# Top.net
KiCad netlist of a schematic drawn in EAGLE
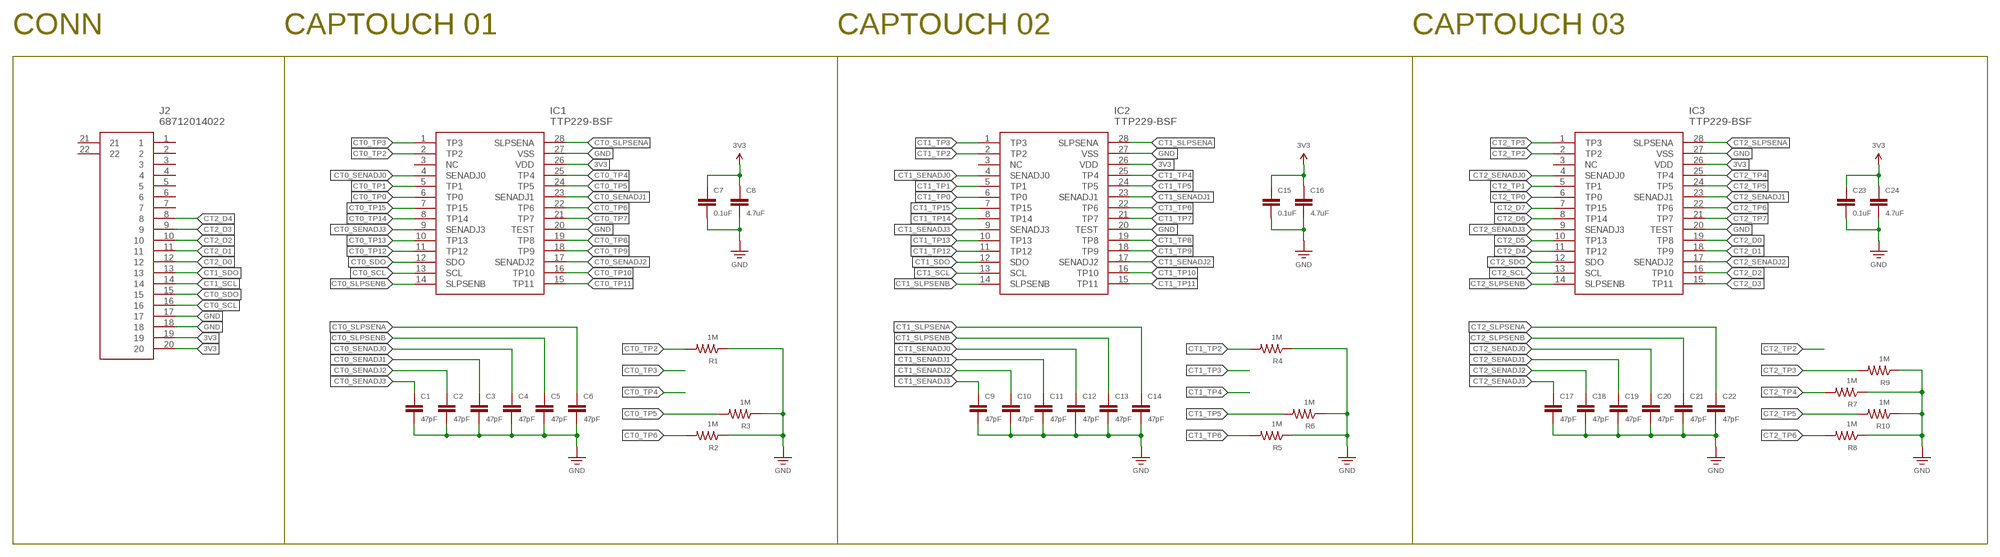
[diagram p0: schematic, sheet 1]

(export (version "E")
  (design (tool "Eeschema 10.0.6"))
  (components
    (comp (ref "C1")
      (value "47pF")
      (footprint "eagle-import:CAP-0603")
      (libsource (lib "eagle-import") (part "CAP-0603"))
    )
    (comp (ref "C2")
      (value "47pF")
      (footprint "eagle-import:CAP-0603")
      (libsource (lib "eagle-import") (part "CAP-0603"))
    )
    (comp (ref "C3")
      (value "47pF")
      (footprint "eagle-import:CAP-0603")
      (libsource (lib "eagle-import") (part "CAP-0603"))
    )
    (comp (ref "C4")
      (value "47pF")
      (footprint "eagle-import:CAP-0603")
      (libsource (lib "eagle-import") (part "CAP-0603"))
    )
    (comp (ref "C5")
      (value "47pF")
      (footprint "eagle-import:CAP-0603")
      (libsource (lib "eagle-import") (part "CAP-0603"))
    )
    (comp (ref "C6")
      (value "47pF")
      (footprint "eagle-import:CAP-0603")
      (libsource (lib "eagle-import") (part "CAP-0603"))
    )
    (comp (ref "C7")
      (value "0.1uF")
      (footprint "eagle-import:CAP-0603")
      (libsource (lib "eagle-import") (part "CAP-0603"))
    )
    (comp (ref "C8")
      (value "4.7uF")
      (footprint "eagle-import:CAP-0603")
      (libsource (lib "eagle-import") (part "CAP-0603"))
    )
    (comp (ref "C9")
      (value "47pF")
      (footprint "eagle-import:CAP-0603")
      (libsource (lib "eagle-import") (part "CAP-0603"))
    )
    (comp (ref "C10")
      (value "47pF")
      (footprint "eagle-import:CAP-0603")
      (libsource (lib "eagle-import") (part "CAP-0603"))
    )
    (comp (ref "C11")
      (value "47pF")
      (footprint "eagle-import:CAP-0603")
      (libsource (lib "eagle-import") (part "CAP-0603"))
    )
    (comp (ref "C12")
      (value "47pF")
      (footprint "eagle-import:CAP-0603")
      (libsource (lib "eagle-import") (part "CAP-0603"))
    )
    (comp (ref "C13")
      (value "47pF")
      (footprint "eagle-import:CAP-0603")
      (libsource (lib "eagle-import") (part "CAP-0603"))
    )
    (comp (ref "C14")
      (value "47pF")
      (footprint "eagle-import:CAP-0603")
      (libsource (lib "eagle-import") (part "CAP-0603"))
    )
    (comp (ref "C15")
      (value "0.1uF")
      (footprint "eagle-import:CAP-0603")
      (libsource (lib "eagle-import") (part "CAP-0603"))
    )
    (comp (ref "C16")
      (value "4.7uF")
      (footprint "eagle-import:CAP-0603")
      (libsource (lib "eagle-import") (part "CAP-0603"))
    )
    (comp (ref "C17")
      (value "47pF")
      (footprint "eagle-import:CAP-0603")
      (libsource (lib "eagle-import") (part "CAP-0603"))
    )
    (comp (ref "C18")
      (value "47pF")
      (footprint "eagle-import:CAP-0603")
      (libsource (lib "eagle-import") (part "CAP-0603"))
    )
    (comp (ref "C19")
      (value "47pF")
      (footprint "eagle-import:CAP-0603")
      (libsource (lib "eagle-import") (part "CAP-0603"))
    )
    (comp (ref "C20")
      (value "47pF")
      (footprint "eagle-import:CAP-0603")
      (libsource (lib "eagle-import") (part "CAP-0603"))
    )
    (comp (ref "C21")
      (value "47pF")
      (footprint "eagle-import:CAP-0603")
      (libsource (lib "eagle-import") (part "CAP-0603"))
    )
    (comp (ref "C22")
      (value "47pF")
      (footprint "eagle-import:CAP-0603")
      (libsource (lib "eagle-import") (part "CAP-0603"))
    )
    (comp (ref "C23")
      (value "0.1uF")
      (footprint "eagle-import:CAP-0603")
      (libsource (lib "eagle-import") (part "CAP-0603"))
    )
    (comp (ref "C24")
      (value "4.7uF")
      (footprint "eagle-import:CAP-0603")
      (libsource (lib "eagle-import") (part "CAP-0603"))
    )
    (comp (ref "IC1")
      (value "TTP229-BSF")
      (footprint "eagle-import:SOP64P600X175-28N")
      (libsource (lib "eagle-import") (part "TTP229-BSF"))
    )
    (comp (ref "IC2")
      (value "TTP229-BSF")
      (footprint "eagle-import:SOP64P600X175-28N")
      (libsource (lib "eagle-import") (part "TTP229-BSF"))
    )
    (comp (ref "IC3")
      (value "TTP229-BSF")
      (footprint "eagle-import:SOP64P600X175-28N")
      (libsource (lib "eagle-import") (part "TTP229-BSF"))
    )
    (comp (ref "J2")
      (value "68712014022")
      (footprint "eagle-import:68712014022")
      (fields (field (name "MOUSER_PART_NUMBER") "710-68712014022"))
      (libsource (lib "eagle-import") (part "68712014022"))
    )
    (comp (ref "R1")
      (value "1M")
      (footprint "eagle-import:RES-0603")
      (libsource (lib "eagle-import") (part "RES-0603"))
    )
    (comp (ref "R2")
      (value "1M")
      (footprint "eagle-import:RES-0603")
      (libsource (lib "eagle-import") (part "RES-0603"))
    )
    (comp (ref "R3")
      (value "1M")
      (footprint "eagle-import:RES-0603")
      (libsource (lib "eagle-import") (part "RES-0603"))
    )
    (comp (ref "R4")
      (value "1M")
      (footprint "eagle-import:RES-0603")
      (libsource (lib "eagle-import") (part "RES-0603"))
    )
    (comp (ref "R5")
      (value "1M")
      (footprint "eagle-import:RES-0603")
      (libsource (lib "eagle-import") (part "RES-0603"))
    )
    (comp (ref "R6")
      (value "1M")
      (footprint "eagle-import:RES-0603")
      (libsource (lib "eagle-import") (part "RES-0603"))
    )
    (comp (ref "R7")
      (value "1M")
      (footprint "eagle-import:RES-0603")
      (libsource (lib "eagle-import") (part "RES-0603"))
    )
    (comp (ref "R8")
      (value "1M")
      (footprint "eagle-import:RES-0603")
      (libsource (lib "eagle-import") (part "RES-0603"))
    )
    (comp (ref "R9")
      (value "1M")
      (footprint "eagle-import:RES-0603")
      (libsource (lib "eagle-import") (part "RES-0603"))
    )
    (comp (ref "R10")
      (value "1M")
      (footprint "eagle-import:RES-0603")
      (libsource (lib "eagle-import") (part "RES-0603"))
    )
  )
  (nets
    (net (code "1") (name "3V3") (class "Default")
      (node (ref "C15") (pin "P$1") (pinfunction "1_P$1") (pintype "passive"))
      (node (ref "C16") (pin "P$1") (pinfunction "1_P$1") (pintype "passive"))
      (node (ref "C23") (pin "P$1") (pinfunction "1_P$1") (pintype "passive"))
      (node (ref "C24") (pin "P$1") (pinfunction "1_P$1") (pintype "passive"))
      (node (ref "C7") (pin "P$1") (pinfunction "1_P$1") (pintype "passive"))
      (node (ref "C8") (pin "P$1") (pinfunction "1_P$1") (pintype "passive"))
      (node (ref "IC1") (pin "26") (pinfunction "VDD_26") (pintype "bidirectional"))
      (node (ref "IC2") (pin "26") (pinfunction "VDD_26") (pintype "bidirectional"))
      (node (ref "IC3") (pin "26") (pinfunction "VDD_26") (pintype "bidirectional"))
      (node (ref "J2") (pin "19") (pinfunction "19_19") (pintype "bidirectional"))
      (node (ref "J2") (pin "20") (pinfunction "20_20") (pintype "bidirectional"))
    )
    (net (code "2") (name "CT0_SCL") (class "Default")
      (node (ref "IC1") (pin "13") (pinfunction "SCL_13") (pintype "bidirectional"))
      (node (ref "J2") (pin "16") (pinfunction "16_16") (pintype "bidirectional"))
    )
    (net (code "3") (name "CT0_SDO") (class "Default")
      (node (ref "IC1") (pin "12") (pinfunction "SDO_12") (pintype "bidirectional"))
      (node (ref "J2") (pin "15") (pinfunction "15_15") (pintype "bidirectional"))
    )
    (net (code "4") (name "CT0_SENADJ0") (class "Default")
      (node (ref "C4") (pin "P$1") (pinfunction "1_P$1") (pintype "passive"))
      (node (ref "IC1") (pin "4") (pinfunction "SENADJ0_4") (pintype "bidirectional"))
    )
    (net (code "5") (name "CT0_SENADJ1") (class "Default")
      (node (ref "C3") (pin "P$1") (pinfunction "1_P$1") (pintype "passive"))
      (node (ref "IC1") (pin "23") (pinfunction "SENADJ1_23") (pintype "bidirectional"))
    )
    (net (code "6") (name "CT0_SENADJ2") (class "Default")
      (node (ref "C2") (pin "P$1") (pinfunction "1_P$1") (pintype "passive"))
      (node (ref "IC1") (pin "17") (pinfunction "SENADJ2_17") (pintype "bidirectional"))
    )
    (net (code "7") (name "CT0_SENADJ3") (class "Default")
      (node (ref "C1") (pin "P$1") (pinfunction "1_P$1") (pintype "passive"))
      (node (ref "IC1") (pin "9") (pinfunction "SENADJ3_9") (pintype "bidirectional"))
    )
    (net (code "8") (name "CT0_SLPSENA") (class "Default")
      (node (ref "C6") (pin "P$1") (pinfunction "1_P$1") (pintype "passive"))
      (node (ref "IC1") (pin "28") (pinfunction "SLPSENA_28") (pintype "bidirectional"))
    )
    (net (code "9") (name "CT0_SLPSENB") (class "Default")
      (node (ref "C5") (pin "P$1") (pinfunction "1_P$1") (pintype "passive"))
      (node (ref "IC1") (pin "14") (pinfunction "SLPSENB_14") (pintype "bidirectional"))
    )
    (net (code "10") (name "CT0_TP0") (class "Default")
      (node (ref "IC1") (pin "6") (pinfunction "TP0_6") (pintype "bidirectional"))
    )
    (net (code "11") (name "CT0_TP1") (class "Default")
      (node (ref "IC1") (pin "5") (pinfunction "TP1_5") (pintype "bidirectional"))
    )
    (net (code "12") (name "CT0_TP2") (class "Default")
      (node (ref "IC1") (pin "2") (pinfunction "TP2_2") (pintype "bidirectional"))
      (node (ref "R1") (pin "P$2") (pinfunction "2_P$2") (pintype "passive"))
    )
    (net (code "13") (name "CT0_TP3") (class "Default")
      (node (ref "IC1") (pin "1") (pinfunction "TP3_1") (pintype "bidirectional"))
    )
    (net (code "14") (name "CT0_TP4") (class "Default")
      (node (ref "IC1") (pin "25") (pinfunction "TP4_25") (pintype "bidirectional"))
    )
    (net (code "15") (name "CT0_TP5") (class "Default")
      (node (ref "IC1") (pin "24") (pinfunction "TP5_24") (pintype "bidirectional"))
      (node (ref "R3") (pin "P$2") (pinfunction "2_P$2") (pintype "passive"))
    )
    (net (code "16") (name "CT0_TP6") (class "Default")
      (node (ref "IC1") (pin "22") (pinfunction "TP6_22") (pintype "bidirectional"))
      (node (ref "R2") (pin "P$2") (pinfunction "2_P$2") (pintype "passive"))
    )
    (net (code "17") (name "CT0_TP7") (class "Default")
      (node (ref "IC1") (pin "21") (pinfunction "TP7_21") (pintype "bidirectional"))
    )
    (net (code "18") (name "CT0_TP8") (class "Default")
      (node (ref "IC1") (pin "19") (pinfunction "TP8_19") (pintype "bidirectional"))
    )
    (net (code "19") (name "CT0_TP9") (class "Default")
      (node (ref "IC1") (pin "18") (pinfunction "TP9_18") (pintype "bidirectional"))
    )
    (net (code "20") (name "CT0_TP10") (class "Default")
      (node (ref "IC1") (pin "16") (pinfunction "TP10_16") (pintype "bidirectional"))
    )
    (net (code "21") (name "CT0_TP11") (class "Default")
      (node (ref "IC1") (pin "15") (pinfunction "TP11_15") (pintype "bidirectional"))
    )
    (net (code "22") (name "CT0_TP12") (class "Default")
      (node (ref "IC1") (pin "11") (pinfunction "TP12_11") (pintype "bidirectional"))
    )
    (net (code "23") (name "CT0_TP13") (class "Default")
      (node (ref "IC1") (pin "10") (pinfunction "TP13_10") (pintype "bidirectional"))
    )
    (net (code "24") (name "CT0_TP14") (class "Default")
      (node (ref "IC1") (pin "8") (pinfunction "TP14_8") (pintype "bidirectional"))
    )
    (net (code "25") (name "CT0_TP15") (class "Default")
      (node (ref "IC1") (pin "7") (pinfunction "TP15_7") (pintype "bidirectional"))
    )
    (net (code "26") (name "CT1_SCL") (class "Default")
      (node (ref "IC2") (pin "13") (pinfunction "SCL_13") (pintype "bidirectional"))
      (node (ref "J2") (pin "14") (pinfunction "14_14") (pintype "bidirectional"))
    )
    (net (code "27") (name "CT1_SDO") (class "Default")
      (node (ref "IC2") (pin "12") (pinfunction "SDO_12") (pintype "bidirectional"))
      (node (ref "J2") (pin "13") (pinfunction "13_13") (pintype "bidirectional"))
    )
    (net (code "28") (name "CT1_SENADJ0") (class "Default")
      (node (ref "C12") (pin "P$1") (pinfunction "1_P$1") (pintype "passive"))
      (node (ref "IC2") (pin "4") (pinfunction "SENADJ0_4") (pintype "bidirectional"))
    )
    (net (code "29") (name "CT1_SENADJ1") (class "Default")
      (node (ref "C11") (pin "P$1") (pinfunction "1_P$1") (pintype "passive"))
      (node (ref "IC2") (pin "23") (pinfunction "SENADJ1_23") (pintype "bidirectional"))
    )
    (net (code "30") (name "CT1_SENADJ2") (class "Default")
      (node (ref "C10") (pin "P$1") (pinfunction "1_P$1") (pintype "passive"))
      (node (ref "IC2") (pin "17") (pinfunction "SENADJ2_17") (pintype "bidirectional"))
    )
    (net (code "31") (name "CT1_SENADJ3") (class "Default")
      (node (ref "C9") (pin "P$1") (pinfunction "1_P$1") (pintype "passive"))
      (node (ref "IC2") (pin "9") (pinfunction "SENADJ3_9") (pintype "bidirectional"))
    )
    (net (code "32") (name "CT1_SLPSENA") (class "Default")
      (node (ref "C14") (pin "P$1") (pinfunction "1_P$1") (pintype "passive"))
      (node (ref "IC2") (pin "28") (pinfunction "SLPSENA_28") (pintype "bidirectional"))
    )
    (net (code "33") (name "CT1_SLPSENB") (class "Default")
      (node (ref "C13") (pin "P$1") (pinfunction "1_P$1") (pintype "passive"))
      (node (ref "IC2") (pin "14") (pinfunction "SLPSENB_14") (pintype "bidirectional"))
    )
    (net (code "34") (name "CT1_TP0") (class "Default")
      (node (ref "IC2") (pin "6") (pinfunction "TP0_6") (pintype "bidirectional"))
    )
    (net (code "35") (name "CT1_TP1") (class "Default")
      (node (ref "IC2") (pin "5") (pinfunction "TP1_5") (pintype "bidirectional"))
    )
    (net (code "36") (name "CT1_TP2") (class "Default")
      (node (ref "IC2") (pin "2") (pinfunction "TP2_2") (pintype "bidirectional"))
      (node (ref "R4") (pin "P$2") (pinfunction "2_P$2") (pintype "passive"))
    )
    (net (code "37") (name "CT1_TP3") (class "Default")
      (node (ref "IC2") (pin "1") (pinfunction "TP3_1") (pintype "bidirectional"))
    )
    (net (code "38") (name "CT1_TP4") (class "Default")
      (node (ref "IC2") (pin "25") (pinfunction "TP4_25") (pintype "bidirectional"))
    )
    (net (code "39") (name "CT1_TP5") (class "Default")
      (node (ref "IC2") (pin "24") (pinfunction "TP5_24") (pintype "bidirectional"))
      (node (ref "R6") (pin "P$2") (pinfunction "2_P$2") (pintype "passive"))
    )
    (net (code "40") (name "CT1_TP6") (class "Default")
      (node (ref "IC2") (pin "22") (pinfunction "TP6_22") (pintype "bidirectional"))
      (node (ref "R5") (pin "P$2") (pinfunction "2_P$2") (pintype "passive"))
    )
    (net (code "41") (name "CT1_TP7") (class "Default")
      (node (ref "IC2") (pin "21") (pinfunction "TP7_21") (pintype "bidirectional"))
    )
    (net (code "42") (name "CT1_TP8") (class "Default")
      (node (ref "IC2") (pin "19") (pinfunction "TP8_19") (pintype "bidirectional"))
    )
    (net (code "43") (name "CT1_TP9") (class "Default")
      (node (ref "IC2") (pin "18") (pinfunction "TP9_18") (pintype "bidirectional"))
    )
    (net (code "44") (name "CT1_TP10") (class "Default")
      (node (ref "IC2") (pin "16") (pinfunction "TP10_16") (pintype "bidirectional"))
    )
    (net (code "45") (name "CT1_TP11") (class "Default")
      (node (ref "IC2") (pin "15") (pinfunction "TP11_15") (pintype "bidirectional"))
    )
    (net (code "46") (name "CT1_TP12") (class "Default")
      (node (ref "IC2") (pin "11") (pinfunction "TP12_11") (pintype "bidirectional"))
    )
    (net (code "47") (name "CT1_TP13") (class "Default")
      (node (ref "IC2") (pin "10") (pinfunction "TP13_10") (pintype "bidirectional"))
    )
    (net (code "48") (name "CT1_TP14") (class "Default")
      (node (ref "IC2") (pin "8") (pinfunction "TP14_8") (pintype "bidirectional"))
    )
    (net (code "49") (name "CT1_TP15") (class "Default")
      (node (ref "IC2") (pin "7") (pinfunction "TP15_7") (pintype "bidirectional"))
    )
    (net (code "50") (name "CT2_D0") (class "Default")
      (node (ref "IC3") (pin "19") (pinfunction "TP8_19") (pintype "bidirectional"))
      (node (ref "J2") (pin "12") (pinfunction "12_12") (pintype "bidirectional"))
    )
    (net (code "51") (name "CT2_D1") (class "Default")
      (node (ref "IC3") (pin "18") (pinfunction "TP9_18") (pintype "bidirectional"))
      (node (ref "J2") (pin "11") (pinfunction "11_11") (pintype "bidirectional"))
    )
    (net (code "52") (name "CT2_D2") (class "Default")
      (node (ref "IC3") (pin "16") (pinfunction "TP10_16") (pintype "bidirectional"))
      (node (ref "J2") (pin "10") (pinfunction "10_10") (pintype "bidirectional"))
    )
    (net (code "53") (name "CT2_D3") (class "Default")
      (node (ref "IC3") (pin "15") (pinfunction "TP11_15") (pintype "bidirectional"))
      (node (ref "J2") (pin "9") (pinfunction "9_9") (pintype "bidirectional"))
    )
    (net (code "54") (name "CT2_D4") (class "Default")
      (node (ref "IC3") (pin "11") (pinfunction "TP12_11") (pintype "bidirectional"))
      (node (ref "J2") (pin "8") (pinfunction "8_8") (pintype "bidirectional"))
    )
    (net (code "55") (name "CT2_D5") (class "Default")
      (node (ref "IC3") (pin "10") (pinfunction "TP13_10") (pintype "bidirectional"))
    )
    (net (code "56") (name "CT2_D6") (class "Default")
      (node (ref "IC3") (pin "8") (pinfunction "TP14_8") (pintype "bidirectional"))
    )
    (net (code "57") (name "CT2_D7") (class "Default")
      (node (ref "IC3") (pin "7") (pinfunction "TP15_7") (pintype "bidirectional"))
    )
    (net (code "58") (name "CT2_SCL") (class "Default")
      (node (ref "IC3") (pin "13") (pinfunction "SCL_13") (pintype "bidirectional"))
    )
    (net (code "59") (name "CT2_SDO") (class "Default")
      (node (ref "IC3") (pin "12") (pinfunction "SDO_12") (pintype "bidirectional"))
    )
    (net (code "60") (name "CT2_SENADJ0") (class "Default")
      (node (ref "C20") (pin "P$1") (pinfunction "1_P$1") (pintype "passive"))
      (node (ref "IC3") (pin "4") (pinfunction "SENADJ0_4") (pintype "bidirectional"))
    )
    (net (code "61") (name "CT2_SENADJ1") (class "Default")
      (node (ref "C19") (pin "P$1") (pinfunction "1_P$1") (pintype "passive"))
      (node (ref "IC3") (pin "23") (pinfunction "SENADJ1_23") (pintype "bidirectional"))
    )
    (net (code "62") (name "CT2_SENADJ2") (class "Default")
      (node (ref "C18") (pin "P$1") (pinfunction "1_P$1") (pintype "passive"))
      (node (ref "IC3") (pin "17") (pinfunction "SENADJ2_17") (pintype "bidirectional"))
    )
    (net (code "63") (name "CT2_SENADJ3") (class "Default")
      (node (ref "C17") (pin "P$1") (pinfunction "1_P$1") (pintype "passive"))
      (node (ref "IC3") (pin "9") (pinfunction "SENADJ3_9") (pintype "bidirectional"))
    )
    (net (code "64") (name "CT2_SLPSENA") (class "Default")
      (node (ref "C22") (pin "P$1") (pinfunction "1_P$1") (pintype "passive"))
      (node (ref "IC3") (pin "28") (pinfunction "SLPSENA_28") (pintype "bidirectional"))
    )
    (net (code "65") (name "CT2_SLPSENB") (class "Default")
      (node (ref "C21") (pin "P$1") (pinfunction "1_P$1") (pintype "passive"))
      (node (ref "IC3") (pin "14") (pinfunction "SLPSENB_14") (pintype "bidirectional"))
    )
    (net (code "66") (name "CT2_TP0") (class "Default")
      (node (ref "IC3") (pin "6") (pinfunction "TP0_6") (pintype "bidirectional"))
    )
    (net (code "67") (name "CT2_TP1") (class "Default")
      (node (ref "IC3") (pin "5") (pinfunction "TP1_5") (pintype "bidirectional"))
    )
    (net (code "68") (name "CT2_TP2") (class "Default")
      (node (ref "IC3") (pin "2") (pinfunction "TP2_2") (pintype "bidirectional"))
    )
    (net (code "69") (name "CT2_TP3") (class "Default")
      (node (ref "IC3") (pin "1") (pinfunction "TP3_1") (pintype "bidirectional"))
      (node (ref "R9") (pin "P$2") (pinfunction "2_P$2") (pintype "passive"))
    )
    (net (code "70") (name "CT2_TP4") (class "Default")
      (node (ref "IC3") (pin "25") (pinfunction "TP4_25") (pintype "bidirectional"))
      (node (ref "R7") (pin "P$2") (pinfunction "2_P$2") (pintype "passive"))
    )
    (net (code "71") (name "CT2_TP5") (class "Default")
      (node (ref "IC3") (pin "24") (pinfunction "TP5_24") (pintype "bidirectional"))
      (node (ref "R10") (pin "P$2") (pinfunction "2_P$2") (pintype "passive"))
    )
    (net (code "72") (name "CT2_TP6") (class "Default")
      (node (ref "IC3") (pin "22") (pinfunction "TP6_22") (pintype "bidirectional"))
      (node (ref "R8") (pin "P$2") (pinfunction "2_P$2") (pintype "passive"))
    )
    (net (code "73") (name "CT2_TP7") (class "Default")
      (node (ref "IC3") (pin "21") (pinfunction "TP7_21") (pintype "bidirectional"))
    )
    (net (code "74") (name "GND") (class "Default")
      (node (ref "C1") (pin "P$2") (pinfunction "2_P$2") (pintype "passive"))
      (node (ref "C10") (pin "P$2") (pinfunction "2_P$2") (pintype "passive"))
      (node (ref "C11") (pin "P$2") (pinfunction "2_P$2") (pintype "passive"))
      (node (ref "C12") (pin "P$2") (pinfunction "2_P$2") (pintype "passive"))
      (node (ref "C13") (pin "P$2") (pinfunction "2_P$2") (pintype "passive"))
      (node (ref "C14") (pin "P$2") (pinfunction "2_P$2") (pintype "passive"))
      (node (ref "C15") (pin "P$2") (pinfunction "2_P$2") (pintype "passive"))
      (node (ref "C16") (pin "P$2") (pinfunction "2_P$2") (pintype "passive"))
      (node (ref "C17") (pin "P$2") (pinfunction "2_P$2") (pintype "passive"))
      (node (ref "C18") (pin "P$2") (pinfunction "2_P$2") (pintype "passive"))
      (node (ref "C19") (pin "P$2") (pinfunction "2_P$2") (pintype "passive"))
      (node (ref "C2") (pin "P$2") (pinfunction "2_P$2") (pintype "passive"))
      (node (ref "C20") (pin "P$2") (pinfunction "2_P$2") (pintype "passive"))
      (node (ref "C21") (pin "P$2") (pinfunction "2_P$2") (pintype "passive"))
      (node (ref "C22") (pin "P$2") (pinfunction "2_P$2") (pintype "passive"))
      (node (ref "C23") (pin "P$2") (pinfunction "2_P$2") (pintype "passive"))
      (node (ref "C24") (pin "P$2") (pinfunction "2_P$2") (pintype "passive"))
      (node (ref "C3") (pin "P$2") (pinfunction "2_P$2") (pintype "passive"))
      (node (ref "C4") (pin "P$2") (pinfunction "2_P$2") (pintype "passive"))
      (node (ref "C5") (pin "P$2") (pinfunction "2_P$2") (pintype "passive"))
      (node (ref "C6") (pin "P$2") (pinfunction "2_P$2") (pintype "passive"))
      (node (ref "C7") (pin "P$2") (pinfunction "2_P$2") (pintype "passive"))
      (node (ref "C8") (pin "P$2") (pinfunction "2_P$2") (pintype "passive"))
      (node (ref "C9") (pin "P$2") (pinfunction "2_P$2") (pintype "passive"))
      (node (ref "IC1") (pin "20") (pinfunction "TEST_20") (pintype "bidirectional"))
      (node (ref "IC1") (pin "27") (pinfunction "VSS_27") (pintype "bidirectional"))
      (node (ref "IC2") (pin "20") (pinfunction "TEST_20") (pintype "bidirectional"))
      (node (ref "IC2") (pin "27") (pinfunction "VSS_27") (pintype "bidirectional"))
      (node (ref "IC3") (pin "20") (pinfunction "TEST_20") (pintype "bidirectional"))
      (node (ref "IC3") (pin "27") (pinfunction "VSS_27") (pintype "bidirectional"))
      (node (ref "J2") (pin "17") (pinfunction "17_17") (pintype "bidirectional"))
      (node (ref "J2") (pin "18") (pinfunction "18_18") (pintype "bidirectional"))
      (node (ref "R1") (pin "P$1") (pinfunction "1_P$1") (pintype "passive"))
      (node (ref "R10") (pin "P$1") (pinfunction "1_P$1") (pintype "passive"))
      (node (ref "R2") (pin "P$1") (pinfunction "1_P$1") (pintype "passive"))
      (node (ref "R3") (pin "P$1") (pinfunction "1_P$1") (pintype "passive"))
      (node (ref "R4") (pin "P$1") (pinfunction "1_P$1") (pintype "passive"))
      (node (ref "R5") (pin "P$1") (pinfunction "1_P$1") (pintype "passive"))
      (node (ref "R6") (pin "P$1") (pinfunction "1_P$1") (pintype "passive"))
      (node (ref "R7") (pin "P$1") (pinfunction "1_P$1") (pintype "passive"))
      (node (ref "R8") (pin "P$1") (pinfunction "1_P$1") (pintype "passive"))
      (node (ref "R9") (pin "P$1") (pinfunction "1_P$1") (pintype "passive"))
    )
    (net (code "75") (name "unconnected-(IC1-NC-Pad3)") (class "Default")
      (node (ref "IC1") (pin "3") (pinfunction "NC_3") (pintype "no_connect"))
    )
    (net (code "76") (name "unconnected-(IC2-NC-Pad3)") (class "Default")
      (node (ref "IC2") (pin "3") (pinfunction "NC_3") (pintype "no_connect"))
    )
    (net (code "77") (name "unconnected-(IC3-NC-Pad3)") (class "Default")
      (node (ref "IC3") (pin "3") (pinfunction "NC_3") (pintype "no_connect"))
    )
    (net (code "78") (name "unconnected-(J2-Pad1)") (class "Default")
      (node (ref "J2") (pin "1") (pinfunction "1_1") (pintype "bidirectional"))
    )
    (net (code "79") (name "unconnected-(J2-Pad2)") (class "Default")
      (node (ref "J2") (pin "2") (pinfunction "2_2") (pintype "bidirectional"))
    )
    (net (code "80") (name "unconnected-(J2-Pad3)") (class "Default")
      (node (ref "J2") (pin "3") (pinfunction "3_3") (pintype "bidirectional"))
    )
    (net (code "81") (name "unconnected-(J2-Pad4)") (class "Default")
      (node (ref "J2") (pin "4") (pinfunction "4_4") (pintype "bidirectional"))
    )
    (net (code "82") (name "unconnected-(J2-Pad5)") (class "Default")
      (node (ref "J2") (pin "5") (pinfunction "5_5") (pintype "bidirectional"))
    )
    (net (code "83") (name "unconnected-(J2-Pad6)") (class "Default")
      (node (ref "J2") (pin "6") (pinfunction "6_6") (pintype "bidirectional"))
    )
    (net (code "84") (name "unconnected-(J2-Pad7)") (class "Default")
      (node (ref "J2") (pin "7") (pinfunction "7_7") (pintype "bidirectional"))
    )
    (net (code "85") (name "unconnected-(J2-Pad21)") (class "Default")
      (node (ref "J2") (pin "21") (pinfunction "21_21") (pintype "bidirectional"))
    )
    (net (code "86") (name "unconnected-(J2-Pad22)") (class "Default")
      (node (ref "J2") (pin "22") (pinfunction "22_22") (pintype "bidirectional"))
    )
  )
)
